# CPU_EBI1_FPGA_Memory.net
KiCad netlist of a schematic drawn in Altium Designer
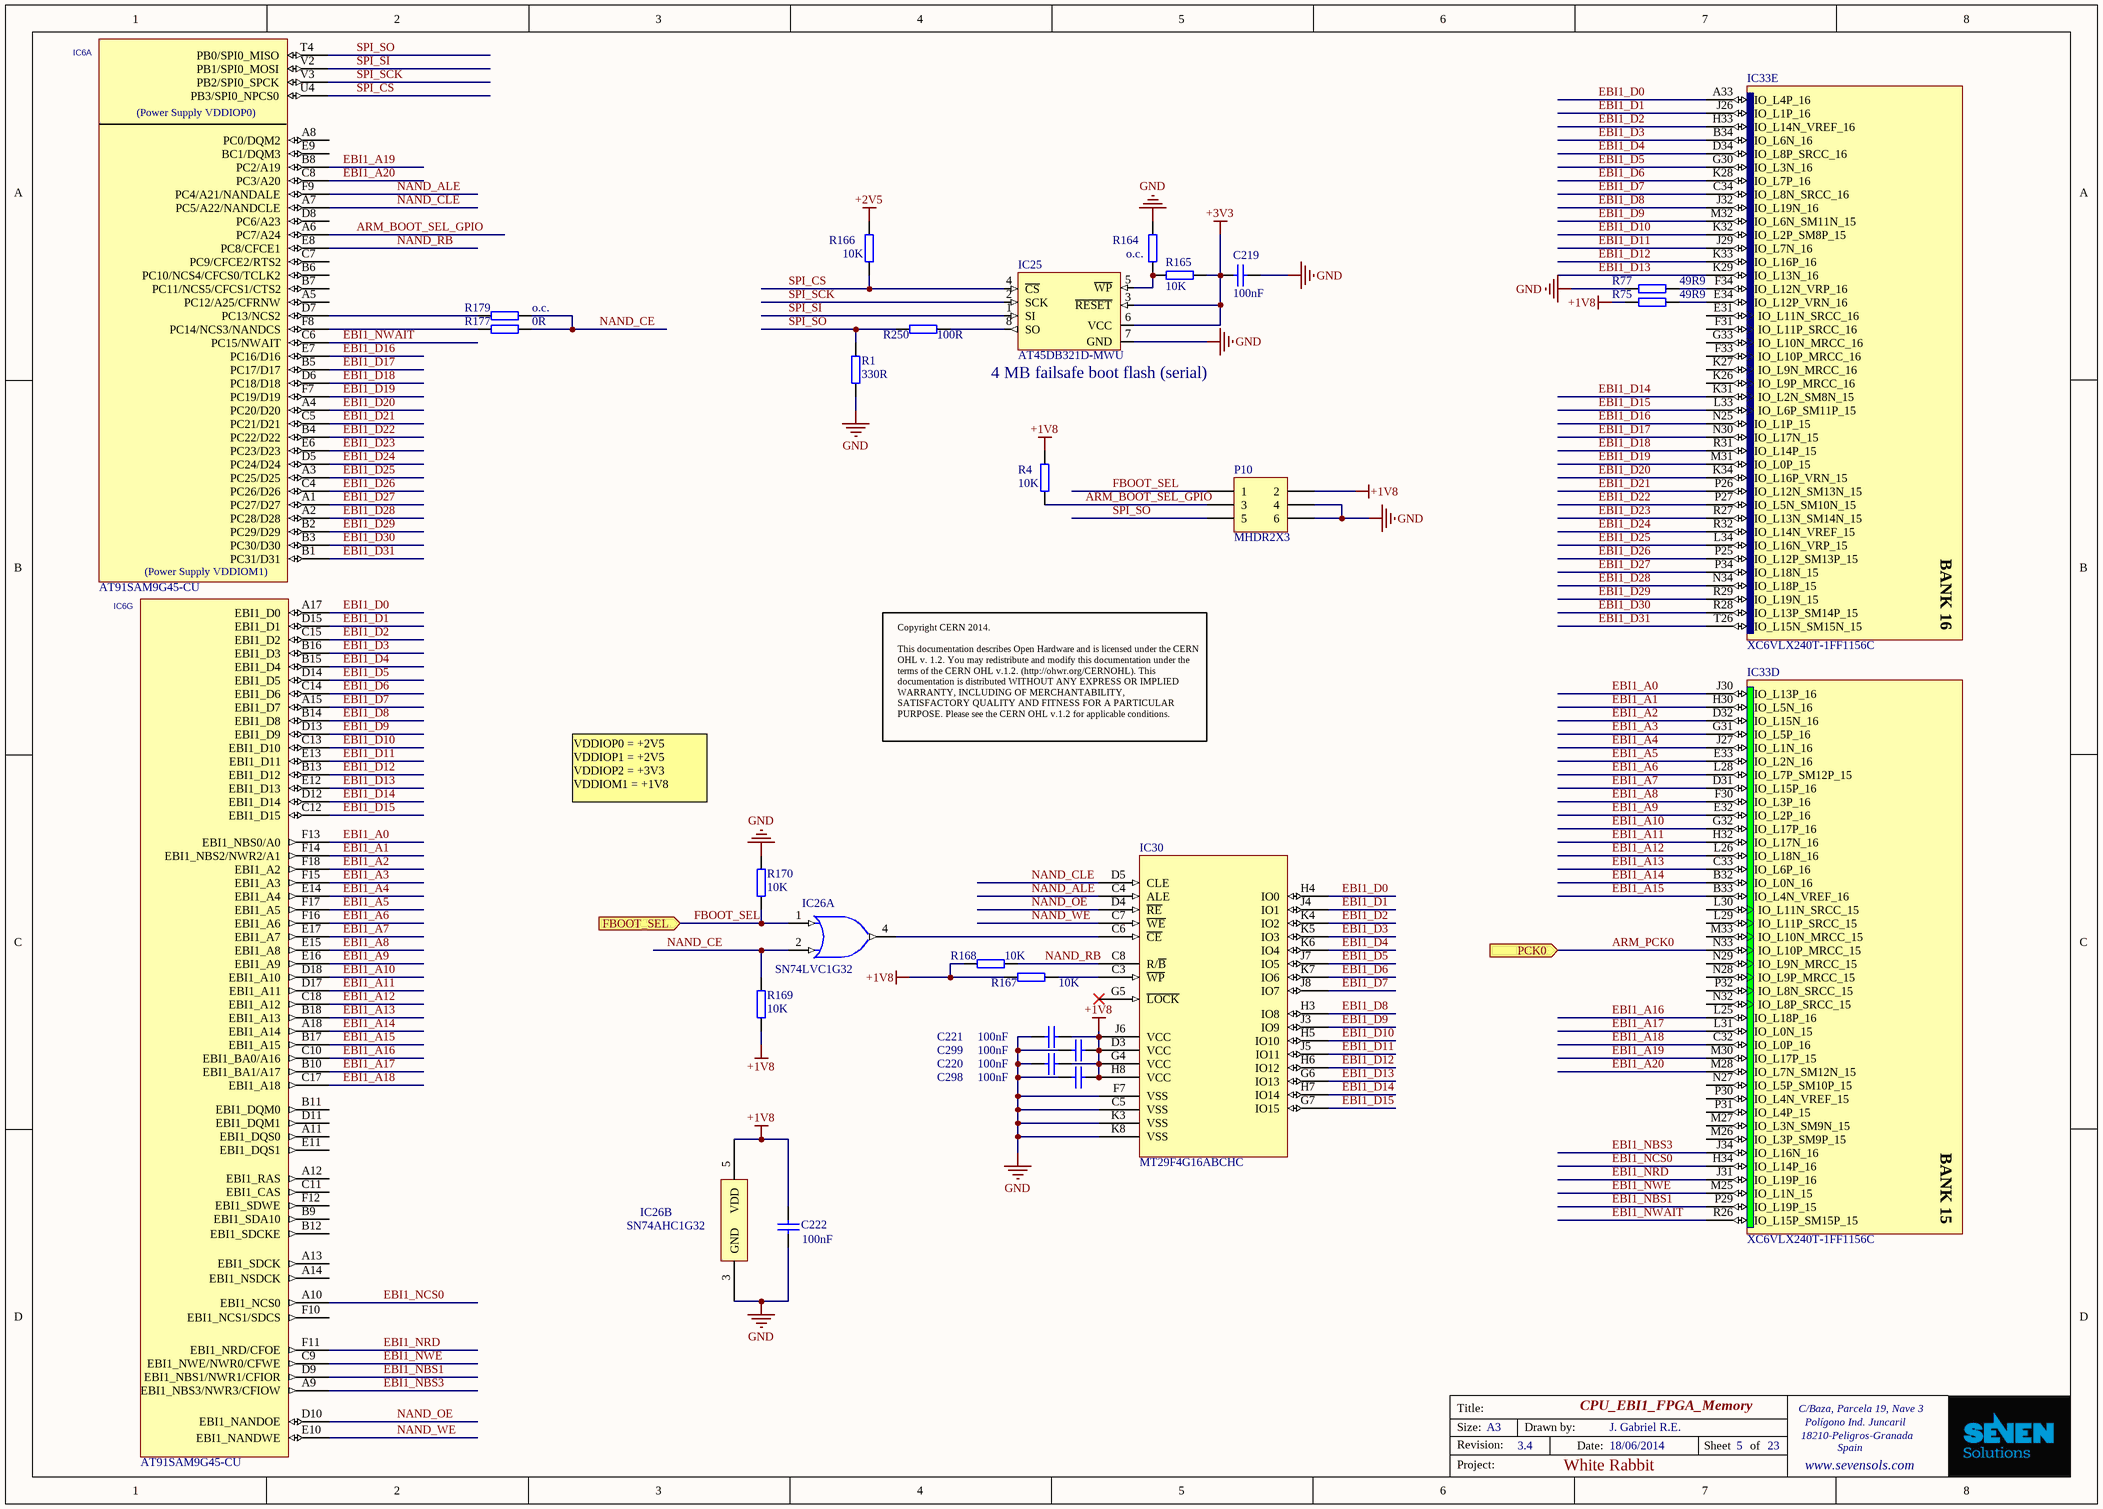
[diagram p0: CPU_EBI1_FPGA_Memory.SchDoc]

(export (version "E")
  (design (tool "Eeschema 10.0.6"))
  (components
    (comp (ref "C219")
      (value "100nF")
      (footprint "CC1005-0402")
      (description "Capacitor")
      (fields
        (field (name "TOLERANCE") "±10%")
        (field (name "VOLTAGE") "16V")
        (field (name "PUBLISHER") "Altium Limited")
      )
      (libsource (lib "wr_switch") (part "Cap"))
    )
    (comp (ref "C220")
      (value "100nF")
      (footprint "CC1005-0402")
      (description "Capacitor")
      (fields
        (field (name "TOLERANCE") "±10%")
        (field (name "VOLTAGE") "16V")
        (field (name "PUBLISHER") "Altium Limited")
      )
      (libsource (lib "wr_switch") (part "Cap"))
    )
    (comp (ref "C221")
      (value "100nF")
      (footprint "CC1005-0402")
      (description "Capacitor")
      (fields
        (field (name "TOLERANCE") "±10%")
        (field (name "VOLTAGE") "16V")
        (field (name "PUBLISHER") "Altium Limited")
      )
      (libsource (lib "wr_switch") (part "Cap"))
    )
    (comp (ref "C222")
      (value "100nF")
      (footprint "CC1005-0402")
      (description "Capacitor")
      (fields
        (field (name "TOLERANCE") "±10%")
        (field (name "VOLTAGE") "16V")
        (field (name "PUBLISHER") "Altium Limited")
      )
      (libsource (lib "wr_switch") (part "Cap"))
    )
    (comp (ref "C298")
      (value "100nF")
      (footprint "CC1005-0402")
      (description "Capacitor")
      (fields
        (field (name "TOLERANCE") "±10%")
        (field (name "VOLTAGE") "16V")
        (field (name "PUBLISHER") "Altium Limited")
      )
      (libsource (lib "wr_switch") (part "Cap"))
    )
    (comp (ref "C299")
      (value "100nF")
      (footprint "CC1005-0402")
      (description "Capacitor")
      (fields
        (field (name "TOLERANCE") "±10%")
        (field (name "VOLTAGE") "16V")
        (field (name "PUBLISHER") "Altium Limited")
      )
      (libsource (lib "wr_switch") (part "Cap"))
    )
    (comp (ref "IC6")
      (value "AT91SAM9G45-CU")
      (footprint "TFBGA324")
      (description "Atmel 400MHz ARM926 MCU")
      (libsource (lib "wr_switch") (part "AT91SAM9G45-CU"))
    )
    (comp (ref "IC25")
      (value "AT45DB321D-MWU")
      (footprint "7S_WR:8MW_8CN3_Merge")
      (description "64-megabit 2.7V, Dual-Interface DataFlash")
      (libsource (lib "wr_switch") (part "AT45DB642D"))
    )
    (comp (ref "IC26")
      (value "SN74LVC1G32")
      (footprint "SOT23-5AL")
      (description "TI single OR gate")
      (libsource (lib "wr_switch") (part "SN74AHC1G32"))
    )
    (comp (ref "IC30")
      (value "MT29F4G16ABCHC")
      (footprint "7S_WR:VFBGA63")
      (description "NAND Flash 256Mx16, 1.8V Asynch/Page")
      (libsource (lib "wr_switch") (part "MT29F4G16ABCHC"))
    )
    (comp (ref "IC33")
      (value "XC6VLX240T-1FF1156C")
      (footprint "FF1156")
      (fields (field (name "PUBLISHER") "Altium Limited"))
      (libsource (lib "") (part "XC6VLX240T-1FF1156C_1"))
    )
    (comp (ref "P10")
      (value "MHDR2X3")
      (footprint "7S_WR:MHDR2X3_1.27mm")
      (description "SMD Header, 3-Pin, Dual row, 2.54mm pitch")
      (libsource (lib "Miscellaneous Connectors") (part "MHDR2X3"))
    )
    (comp (ref "R1")
      (value "330R")
      (footprint "0402")
      (description "SMD Resistor")
      (fields (field (name "TOLERANCE") "±1%"))
      (libsource (lib "wr_switch") (part "RES_SMD"))
    )
    (comp (ref "R4")
      (value "10K")
      (footprint "0402")
      (description "SMD Resistor")
      (fields (field (name "TOLERANCE") "±1%"))
      (libsource (lib "wr_switch") (part "RES_SMD"))
    )
    (comp (ref "R75")
      (value "49R9")
      (footprint "0402")
      (description "SMD Resistor")
      (fields (field (name "TOLERANCE") "±1%"))
      (libsource (lib "wr_switch") (part "RES_SMD"))
    )
    (comp (ref "R77")
      (value "49R9")
      (footprint "0402")
      (description "SMD Resistor")
      (fields (field (name "TOLERANCE") "±1%"))
      (libsource (lib "wr_switch") (part "RES_SMD"))
    )
    (comp (ref "R164")
      (value "o.c.")
      (footprint "0402")
      (description "SMD Resistor")
      (libsource (lib "wr_switch") (part "RES_SMD"))
    )
    (comp (ref "R165")
      (value "10K")
      (footprint "0402")
      (description "SMD Resistor")
      (fields (field (name "TOLERANCE") "±1%"))
      (libsource (lib "wr_switch") (part "RES_SMD"))
    )
    (comp (ref "R166")
      (value "10K")
      (footprint "0402")
      (description "SMD Resistor")
      (fields (field (name "TOLERANCE") "±1%"))
      (libsource (lib "wr_switch") (part "RES_SMD"))
    )
    (comp (ref "R167")
      (value "10K")
      (footprint "0402")
      (description "SMD Resistor")
      (fields (field (name "TOLERANCE") "±1%"))
      (libsource (lib "wr_switch") (part "RES_SMD"))
    )
    (comp (ref "R168")
      (value "10K")
      (footprint "0402")
      (description "SMD Resistor")
      (fields (field (name "TOLERANCE") "±1%"))
      (libsource (lib "wr_switch") (part "RES_SMD"))
    )
    (comp (ref "R169")
      (value "10K")
      (footprint "0402")
      (description "SMD Resistor")
      (fields (field (name "TOLERANCE") "±1%"))
      (libsource (lib "wr_switch") (part "RES_SMD"))
    )
    (comp (ref "R170")
      (value "10K")
      (footprint "0402")
      (description "SMD Resistor")
      (fields (field (name "TOLERANCE") "±1%"))
      (libsource (lib "wr_switch") (part "RES_SMD"))
    )
    (comp (ref "R177")
      (value "0R")
      (footprint "0603")
      (description "SMD Resistor")
      (libsource (lib "wr_switch") (part "RES_SMD"))
    )
    (comp (ref "R179")
      (value "o.c.")
      (footprint "0402")
      (description "SMD Resistor")
      (libsource (lib "wr_switch") (part "RES_SMD"))
    )
    (comp (ref "R250")
      (value "100R")
      (footprint "0402")
      (description "SMD Resistor")
      (fields (field (name "TOLERANCE") "±1%"))
      (libsource (lib "wr_switch") (part "RES_SMD"))
    )
  )
  (nets
    (net (code "1") (name "+1V8") (class "Default")
      (node (ref "C220") (pin "1") (pinfunction "1_1") (pintype "passive"))
      (node (ref "C221") (pin "1") (pinfunction "1_1") (pintype "passive"))
      (node (ref "C222") (pin "2") (pinfunction "2_2") (pintype "passive"))
      (node (ref "C298") (pin "1") (pinfunction "1_1") (pintype "passive"))
      (node (ref "C299") (pin "1") (pinfunction "1_1") (pintype "passive"))
      (node (ref "IC26") (pin "5") (pinfunction "VDD_5") (pintype "passive"))
      (node (ref "IC30") (pin "D3") (pinfunction "VCC_D3") (pintype "power_in"))
      (node (ref "IC30") (pin "G4") (pinfunction "VCC_G4") (pintype "power_in"))
      (node (ref "IC30") (pin "H8") (pinfunction "VCC_H8") (pintype "power_in"))
      (node (ref "IC30") (pin "J6") (pinfunction "VCC_J6") (pintype "power_in"))
      (node (ref "P10") (pin "2") (pinfunction "2_2") (pintype "passive"))
      (node (ref "R167") (pin "2") (pinfunction "2_2") (pintype "passive"))
      (node (ref "R168") (pin "2") (pinfunction "2_2") (pintype "passive"))
      (node (ref "R169") (pin "2") (pinfunction "2_2") (pintype "passive"))
      (node (ref "R4") (pin "2") (pinfunction "2_2") (pintype "passive"))
      (node (ref "R75") (pin "2") (pinfunction "2_2") (pintype "passive"))
    )
    (net (code "2") (name "+2V5") (class "Default")
      (node (ref "R166") (pin "2") (pinfunction "2_2") (pintype "passive"))
    )
    (net (code "3") (name "+3V3") (class "Default")
      (node (ref "C219") (pin "1") (pinfunction "1_1") (pintype "passive"))
      (node (ref "IC25") (pin "3") (pinfunction "~{RESET}_3") (pintype "input"))
      (node (ref "IC25") (pin "6") (pinfunction "VCC_6") (pintype "power_in"))
      (node (ref "R165") (pin "2") (pinfunction "2_2") (pintype "passive"))
    )
    (net (code "4") (name "/ARM_BOOT_SEL_GPIO") (class "Default")
      (node (ref "IC6") (pin "A6") (pinfunction "PC7/A24_A6") (pintype "bidirectional"))
      (node (ref "P10") (pin "3") (pinfunction "3_3") (pintype "passive"))
      (node (ref "R4") (pin "1") (pinfunction "1_1") (pintype "passive"))
    )
    (net (code "5") (name "/ARM_PCK0") (class "Default")
      (node (ref "IC33") (pin "N33") (pinfunction "IO_L10P_MRCC_15_N33") (pintype "bidirectional"))
    )
    (net (code "6") (name "/EBI1_A0") (class "Default")
      (node (ref "IC33") (pin "J30") (pinfunction "IO_L13P_16_J30") (pintype "bidirectional"))
      (node (ref "IC6") (pin "F13") (pinfunction "EBI1_NBS0/A0_F13") (pintype "output"))
    )
    (net (code "7") (name "/EBI1_A1") (class "Default")
      (node (ref "IC33") (pin "H30") (pinfunction "IO_L5N_16_H30") (pintype "bidirectional"))
      (node (ref "IC6") (pin "F14") (pinfunction "EBI1_NBS2/NWR2/A1_F14") (pintype "output"))
    )
    (net (code "8") (name "/EBI1_A2") (class "Default")
      (node (ref "IC33") (pin "D32") (pinfunction "IO_L15N_16_D32") (pintype "bidirectional"))
      (node (ref "IC6") (pin "F18") (pinfunction "EBI1_A2_F18") (pintype "output"))
    )
    (net (code "9") (name "/EBI1_A3") (class "Default")
      (node (ref "IC33") (pin "G31") (pinfunction "IO_L5P_16_G31") (pintype "bidirectional"))
      (node (ref "IC6") (pin "F15") (pinfunction "EBI1_A3_F15") (pintype "output"))
    )
    (net (code "10") (name "/EBI1_A4") (class "Default")
      (node (ref "IC33") (pin "J27") (pinfunction "IO_L1N_16_J27") (pintype "bidirectional"))
      (node (ref "IC6") (pin "E14") (pinfunction "EBI1_A4_E14") (pintype "output"))
    )
    (net (code "11") (name "/EBI1_A5") (class "Default")
      (node (ref "IC33") (pin "E33") (pinfunction "IO_L2N_16_E33") (pintype "bidirectional"))
      (node (ref "IC6") (pin "F17") (pinfunction "EBI1_A5_F17") (pintype "output"))
    )
    (net (code "12") (name "/EBI1_A6") (class "Default")
      (node (ref "IC33") (pin "L28") (pinfunction "IO_L7P_SM12P_15_L28") (pintype "bidirectional"))
      (node (ref "IC6") (pin "F16") (pinfunction "EBI1_A6_F16") (pintype "output"))
    )
    (net (code "13") (name "/EBI1_A7") (class "Default")
      (node (ref "IC33") (pin "D31") (pinfunction "IO_L15P_16_D31") (pintype "bidirectional"))
      (node (ref "IC6") (pin "E17") (pinfunction "EBI1_A7_E17") (pintype "output"))
    )
    (net (code "14") (name "/EBI1_A8") (class "Default")
      (node (ref "IC33") (pin "F30") (pinfunction "IO_L3P_16_F30") (pintype "bidirectional"))
      (node (ref "IC6") (pin "E15") (pinfunction "EBI1_A8_E15") (pintype "output"))
    )
    (net (code "15") (name "/EBI1_A9") (class "Default")
      (node (ref "IC33") (pin "E32") (pinfunction "IO_L2P_16_E32") (pintype "bidirectional"))
      (node (ref "IC6") (pin "E16") (pinfunction "EBI1_A9_E16") (pintype "output"))
    )
    (net (code "16") (name "/EBI1_A10") (class "Default")
      (node (ref "IC33") (pin "G32") (pinfunction "IO_L17P_16_G32") (pintype "bidirectional"))
      (node (ref "IC6") (pin "D18") (pinfunction "EBI1_A10_D18") (pintype "output"))
    )
    (net (code "17") (name "/EBI1_A11") (class "Default")
      (node (ref "IC33") (pin "H32") (pinfunction "IO_L17N_16_H32") (pintype "bidirectional"))
      (node (ref "IC6") (pin "D17") (pinfunction "EBI1_A11_D17") (pintype "output"))
    )
    (net (code "18") (name "/EBI1_A12") (class "Default")
      (node (ref "IC33") (pin "L26") (pinfunction "IO_L18N_16_L26") (pintype "bidirectional"))
      (node (ref "IC6") (pin "C18") (pinfunction "EBI1_A12_C18") (pintype "output"))
    )
    (net (code "19") (name "/EBI1_A13") (class "Default")
      (node (ref "IC33") (pin "C33") (pinfunction "IO_L6P_16_C33") (pintype "bidirectional"))
      (node (ref "IC6") (pin "B18") (pinfunction "EBI1_A13_B18") (pintype "output"))
    )
    (net (code "20") (name "/EBI1_A14") (class "Default")
      (node (ref "IC33") (pin "B32") (pinfunction "IO_L0N_16_B32") (pintype "bidirectional"))
      (node (ref "IC6") (pin "A18") (pinfunction "EBI1_A14_A18") (pintype "output"))
    )
    (net (code "21") (name "/EBI1_A15") (class "Default")
      (node (ref "IC33") (pin "B33") (pinfunction "IO_L4N_VREF_16_B33") (pintype "bidirectional"))
      (node (ref "IC6") (pin "B17") (pinfunction "EBI1_A15_B17") (pintype "output"))
    )
    (net (code "22") (name "/EBI1_A16") (class "Default")
      (node (ref "IC33") (pin "L25") (pinfunction "IO_L18P_16_L25") (pintype "bidirectional"))
      (node (ref "IC6") (pin "C10") (pinfunction "EBI1_BA0/A16_C10") (pintype "output"))
    )
    (net (code "23") (name "/EBI1_A17") (class "Default")
      (node (ref "IC33") (pin "L31") (pinfunction "IO_L0N_15_L31") (pintype "bidirectional"))
      (node (ref "IC6") (pin "B10") (pinfunction "EBI1_BA1/A17_B10") (pintype "output"))
    )
    (net (code "24") (name "/EBI1_A18") (class "Default")
      (node (ref "IC33") (pin "C32") (pinfunction "IO_L0P_16_C32") (pintype "bidirectional"))
      (node (ref "IC6") (pin "C17") (pinfunction "EBI1_A18_C17") (pintype "output"))
    )
    (net (code "25") (name "/EBI1_A19") (class "Default")
      (node (ref "IC33") (pin "M30") (pinfunction "IO_L17P_15_M30") (pintype "bidirectional"))
      (node (ref "IC6") (pin "B8") (pinfunction "PC2/A19_B8") (pintype "bidirectional"))
    )
    (net (code "26") (name "/EBI1_A20") (class "Default")
      (node (ref "IC33") (pin "M28") (pinfunction "IO_L7N_SM12N_15_M28") (pintype "bidirectional"))
      (node (ref "IC6") (pin "C8") (pinfunction "PC3/A20_C8") (pintype "bidirectional"))
    )
    (net (code "27") (name "/EBI1_D0") (class "Default")
      (node (ref "IC30") (pin "H4") (pinfunction "IO0_H4") (pintype "bidirectional"))
      (node (ref "IC33") (pin "A33") (pinfunction "IO_L4P_16_A33") (pintype "bidirectional"))
      (node (ref "IC6") (pin "A17") (pinfunction "EBI1_D0_A17") (pintype "bidirectional"))
    )
    (net (code "28") (name "/EBI1_D1") (class "Default")
      (node (ref "IC30") (pin "J4") (pinfunction "IO1_J4") (pintype "bidirectional"))
      (node (ref "IC33") (pin "J26") (pinfunction "IO_L1P_16_J26") (pintype "bidirectional"))
      (node (ref "IC6") (pin "D15") (pinfunction "EBI1_D1_D15") (pintype "bidirectional"))
    )
    (net (code "29") (name "/EBI1_D2") (class "Default")
      (node (ref "IC30") (pin "K4") (pinfunction "IO2_K4") (pintype "bidirectional"))
      (node (ref "IC33") (pin "H33") (pinfunction "IO_L14N_VREF_16_H33") (pintype "bidirectional"))
      (node (ref "IC6") (pin "C15") (pinfunction "EBI1_D2_C15") (pintype "bidirectional"))
    )
    (net (code "30") (name "/EBI1_D3") (class "Default")
      (node (ref "IC30") (pin "K5") (pinfunction "IO3_K5") (pintype "bidirectional"))
      (node (ref "IC33") (pin "B34") (pinfunction "IO_L6N_16_B34") (pintype "bidirectional"))
      (node (ref "IC6") (pin "B16") (pinfunction "EBI1_D3_B16") (pintype "bidirectional"))
    )
    (net (code "31") (name "/EBI1_D4") (class "Default")
      (node (ref "IC30") (pin "K6") (pinfunction "IO4_K6") (pintype "bidirectional"))
      (node (ref "IC33") (pin "D34") (pinfunction "IO_L8P_SRCC_16_D34") (pintype "bidirectional"))
      (node (ref "IC6") (pin "B15") (pinfunction "EBI1_D4_B15") (pintype "bidirectional"))
    )
    (net (code "32") (name "/EBI1_D5") (class "Default")
      (node (ref "IC30") (pin "J7") (pinfunction "IO5_J7") (pintype "bidirectional"))
      (node (ref "IC33") (pin "G30") (pinfunction "IO_L3N_16_G30") (pintype "bidirectional"))
      (node (ref "IC6") (pin "D14") (pinfunction "EBI1_D5_D14") (pintype "bidirectional"))
    )
    (net (code "33") (name "/EBI1_D6") (class "Default")
      (node (ref "IC30") (pin "K7") (pinfunction "IO6_K7") (pintype "bidirectional"))
      (node (ref "IC33") (pin "K28") (pinfunction "IO_L7P_16_K28") (pintype "bidirectional"))
      (node (ref "IC6") (pin "C14") (pinfunction "EBI1_D6_C14") (pintype "bidirectional"))
    )
    (net (code "34") (name "/EBI1_D7") (class "Default")
      (node (ref "IC30") (pin "J8") (pinfunction "IO7_J8") (pintype "bidirectional"))
      (node (ref "IC33") (pin "C34") (pinfunction "IO_L8N_SRCC_16_C34") (pintype "bidirectional"))
      (node (ref "IC6") (pin "A15") (pinfunction "EBI1_D7_A15") (pintype "bidirectional"))
    )
    (net (code "35") (name "/EBI1_D8") (class "Default")
      (node (ref "IC30") (pin "H3") (pinfunction "IO8_H3") (pintype "bidirectional"))
      (node (ref "IC33") (pin "J32") (pinfunction "IO_L19N_16_J32") (pintype "bidirectional"))
      (node (ref "IC6") (pin "B14") (pinfunction "EBI1_D8_B14") (pintype "bidirectional"))
    )
    (net (code "36") (name "/EBI1_D9") (class "Default")
      (node (ref "IC30") (pin "J3") (pinfunction "IO9_J3") (pintype "bidirectional"))
      (node (ref "IC33") (pin "M32") (pinfunction "IO_L6N_SM11N_15_M32") (pintype "bidirectional"))
      (node (ref "IC6") (pin "D13") (pinfunction "EBI1_D9_D13") (pintype "bidirectional"))
    )
    (net (code "37") (name "/EBI1_D10") (class "Default")
      (node (ref "IC30") (pin "H5") (pinfunction "IO10_H5") (pintype "bidirectional"))
      (node (ref "IC33") (pin "K32") (pinfunction "IO_L2P_SM8P_15_K32") (pintype "bidirectional"))
      (node (ref "IC6") (pin "C13") (pinfunction "EBI1_D10_C13") (pintype "bidirectional"))
    )
    (net (code "38") (name "/EBI1_D11") (class "Default")
      (node (ref "IC30") (pin "J5") (pinfunction "IO11_J5") (pintype "bidirectional"))
      (node (ref "IC33") (pin "J29") (pinfunction "IO_L7N_16_J29") (pintype "bidirectional"))
      (node (ref "IC6") (pin "E13") (pinfunction "EBI1_D11_E13") (pintype "bidirectional"))
    )
    (net (code "39") (name "/EBI1_D12") (class "Default")
      (node (ref "IC30") (pin "H6") (pinfunction "IO12_H6") (pintype "bidirectional"))
      (node (ref "IC33") (pin "K33") (pinfunction "IO_L16P_16_K33") (pintype "bidirectional"))
      (node (ref "IC6") (pin "B13") (pinfunction "EBI1_D12_B13") (pintype "bidirectional"))
    )
    (net (code "40") (name "/EBI1_D13") (class "Default")
      (node (ref "IC30") (pin "G6") (pinfunction "IO13_G6") (pintype "bidirectional"))
      (node (ref "IC33") (pin "K29") (pinfunction "IO_L13N_16_K29") (pintype "bidirectional"))
      (node (ref "IC6") (pin "E12") (pinfunction "EBI1_D13_E12") (pintype "bidirectional"))
    )
    (net (code "41") (name "/EBI1_D14") (class "Default")
      (node (ref "IC30") (pin "H7") (pinfunction "IO14_H7") (pintype "bidirectional"))
      (node (ref "IC33") (pin "K31") (pinfunction "IO_L2N_SM8N_15_K31") (pintype "bidirectional"))
      (node (ref "IC6") (pin "D12") (pinfunction "EBI1_D14_D12") (pintype "bidirectional"))
    )
    (net (code "42") (name "/EBI1_D15") (class "Default")
      (node (ref "IC30") (pin "G7") (pinfunction "IO15_G7") (pintype "bidirectional"))
      (node (ref "IC33") (pin "L33") (pinfunction "IO_L6P_SM11P_15_L33") (pintype "bidirectional"))
      (node (ref "IC6") (pin "C12") (pinfunction "EBI1_D15_C12") (pintype "bidirectional"))
    )
    (net (code "43") (name "/EBI1_D16") (class "Default")
      (node (ref "IC33") (pin "N25") (pinfunction "IO_L1P_15_N25") (pintype "bidirectional"))
      (node (ref "IC6") (pin "E7") (pinfunction "PC16/D16_E7") (pintype "bidirectional"))
    )
    (net (code "44") (name "/EBI1_D17") (class "Default")
      (node (ref "IC33") (pin "N30") (pinfunction "IO_L17N_15_N30") (pintype "bidirectional"))
      (node (ref "IC6") (pin "B5") (pinfunction "PC17/D17_B5") (pintype "bidirectional"))
    )
    (net (code "45") (name "/EBI1_D18") (class "Default")
      (node (ref "IC33") (pin "R31") (pinfunction "IO_L14P_15_R31") (pintype "bidirectional"))
      (node (ref "IC6") (pin "D6") (pinfunction "PC18/D18_D6") (pintype "bidirectional"))
    )
    (net (code "46") (name "/EBI1_D19") (class "Default")
      (node (ref "IC33") (pin "M31") (pinfunction "IO_L0P_15_M31") (pintype "bidirectional"))
      (node (ref "IC6") (pin "F7") (pinfunction "PC19/D19_F7") (pintype "bidirectional"))
    )
    (net (code "47") (name "/EBI1_D20") (class "Default")
      (node (ref "IC33") (pin "K34") (pinfunction "IO_L16P_VRN_15_K34") (pintype "bidirectional"))
      (node (ref "IC6") (pin "A4") (pinfunction "PC20/D20_A4") (pintype "bidirectional"))
    )
    (net (code "48") (name "/EBI1_D21") (class "Default")
      (node (ref "IC33") (pin "P26") (pinfunction "IO_L12N_SM13N_15_P26") (pintype "bidirectional"))
      (node (ref "IC6") (pin "C5") (pinfunction "PC21/D21_C5") (pintype "bidirectional"))
    )
    (net (code "49") (name "/EBI1_D22") (class "Default")
      (node (ref "IC33") (pin "P27") (pinfunction "IO_L5N_SM10N_15_P27") (pintype "bidirectional"))
      (node (ref "IC6") (pin "B4") (pinfunction "PC22/D22_B4") (pintype "bidirectional"))
    )
    (net (code "50") (name "/EBI1_D23") (class "Default")
      (node (ref "IC33") (pin "R27") (pinfunction "IO_L13N_SM14N_15_R27") (pintype "bidirectional"))
      (node (ref "IC6") (pin "E6") (pinfunction "PC23/D23_E6") (pintype "bidirectional"))
    )
    (net (code "51") (name "/EBI1_D24") (class "Default")
      (node (ref "IC33") (pin "R32") (pinfunction "IO_L14N_VREF_15_R32") (pintype "bidirectional"))
      (node (ref "IC6") (pin "D5") (pinfunction "PC24/D24_D5") (pintype "bidirectional"))
    )
    (net (code "52") (name "/EBI1_D25") (class "Default")
      (node (ref "IC33") (pin "L34") (pinfunction "IO_L16N_VRP_15_L34") (pintype "bidirectional"))
      (node (ref "IC6") (pin "A3") (pinfunction "PC25/D25_A3") (pintype "bidirectional"))
    )
    (net (code "53") (name "/EBI1_D26") (class "Default")
      (node (ref "IC33") (pin "P25") (pinfunction "IO_L12P_SM13P_15_P25") (pintype "bidirectional"))
      (node (ref "IC6") (pin "C4") (pinfunction "PC26/D26_C4") (pintype "bidirectional"))
    )
    (net (code "54") (name "/EBI1_D27") (class "Default")
      (node (ref "IC33") (pin "P34") (pinfunction "IO_L18N_15_P34") (pintype "bidirectional"))
      (node (ref "IC6") (pin "A1") (pinfunction "PC27/D27_A1") (pintype "bidirectional"))
    )
    (net (code "55") (name "/EBI1_D28") (class "Default")
      (node (ref "IC33") (pin "N34") (pinfunction "IO_L18P_15_N34") (pintype "bidirectional"))
      (node (ref "IC6") (pin "A2") (pinfunction "PC28/D28_A2") (pintype "bidirectional"))
    )
    (net (code "56") (name "/EBI1_D29") (class "Default")
      (node (ref "IC33") (pin "R29") (pinfunction "IO_L19N_15_R29") (pintype "bidirectional"))
      (node (ref "IC6") (pin "B2") (pinfunction "PC29/D29_B2") (pintype "bidirectional"))
    )
    (net (code "57") (name "/EBI1_D30") (class "Default")
      (node (ref "IC33") (pin "R28") (pinfunction "IO_L13P_SM14P_15_R28") (pintype "bidirectional"))
      (node (ref "IC6") (pin "B3") (pinfunction "PC30/D30_B3") (pintype "bidirectional"))
    )
    (net (code "58") (name "/EBI1_D31") (class "Default")
      (node (ref "IC33") (pin "T26") (pinfunction "IO_L15N_SM15N_15_T26") (pintype "bidirectional"))
      (node (ref "IC6") (pin "B1") (pinfunction "PC31/D31_B1") (pintype "bidirectional"))
    )
    (net (code "59") (name "/EBI1_NBS1") (class "Default")
      (node (ref "IC33") (pin "P29") (pinfunction "IO_L19P_15_P29") (pintype "bidirectional"))
      (node (ref "IC6") (pin "D9") (pinfunction "EBI1_NBS1/NWR1/CFIOR_D9") (pintype "output"))
    )
    (net (code "60") (name "/EBI1_NBS3") (class "Default")
      (node (ref "IC33") (pin "J34") (pinfunction "IO_L16N_16_J34") (pintype "bidirectional"))
      (node (ref "IC6") (pin "A9") (pinfunction "EBI1_NBS3/NWR3/CFIOW_A9") (pintype "output"))
    )
    (net (code "61") (name "/EBI1_NCS0") (class "Default")
      (node (ref "IC33") (pin "H34") (pinfunction "IO_L14P_16_H34") (pintype "bidirectional"))
      (node (ref "IC6") (pin "A10") (pinfunction "EBI1_NCS0_A10") (pintype "output"))
    )
    (net (code "62") (name "/EBI1_NRD") (class "Default")
      (node (ref "IC33") (pin "J31") (pinfunction "IO_L19P_16_J31") (pintype "bidirectional"))
      (node (ref "IC6") (pin "F11") (pinfunction "EBI1_NRD/CFOE_F11") (pintype "output"))
    )
    (net (code "63") (name "/EBI1_NWAIT") (class "Default")
      (node (ref "IC33") (pin "R26") (pinfunction "IO_L15P_SM15P_15_R26") (pintype "bidirectional"))
      (node (ref "IC6") (pin "C6") (pinfunction "PC15/NWAIT_C6") (pintype "bidirectional"))
    )
    (net (code "64") (name "/EBI1_NWE") (class "Default")
      (node (ref "IC33") (pin "M25") (pinfunction "IO_L1N_15_M25") (pintype "bidirectional"))
      (node (ref "IC6") (pin "C9") (pinfunction "EBI1_NWE/NWR0/CFWE_C9") (pintype "output"))
    )
    (net (code "65") (name "/FBOOT_SEL") (class "Default")
      (node (ref "IC26") (pin "1") (pinfunction "A_1") (pintype "input"))
      (node (ref "P10") (pin "1") (pinfunction "1_1") (pintype "passive"))
      (node (ref "R170") (pin "1") (pinfunction "1_1") (pintype "passive"))
    )
    (net (code "66") (name "/NAND_ALE") (class "Default")
      (node (ref "IC30") (pin "C4") (pinfunction "ALE_C4") (pintype "input"))
      (node (ref "IC6") (pin "F9") (pinfunction "PC4/A21/NANDALE_F9") (pintype "bidirectional"))
    )
    (net (code "67") (name "/NAND_CE") (class "Default")
      (node (ref "IC26") (pin "2") (pinfunction "B_2") (pintype "input"))
      (node (ref "R169") (pin "1") (pinfunction "1_1") (pintype "passive"))
      (node (ref "R177") (pin "1") (pinfunction "1_1") (pintype "passive"))
      (node (ref "R179") (pin "1") (pinfunction "1_1") (pintype "passive"))
    )
    (net (code "68") (name "/NAND_CLE") (class "Default")
      (node (ref "IC30") (pin "D5") (pinfunction "CLE_D5") (pintype "input"))
      (node (ref "IC6") (pin "A7") (pinfunction "PC5/A22/NANDCLE_A7") (pintype "bidirectional"))
    )
    (net (code "69") (name "/NAND_OE") (class "Default")
      (node (ref "IC30") (pin "D4") (pinfunction "~{RE}_D4") (pintype "input"))
      (node (ref "IC6") (pin "D10") (pinfunction "EBI1_NANDOE_D10") (pintype "bidirectional"))
    )
    (net (code "70") (name "/NAND_RB") (class "Default")
      (node (ref "IC30") (pin "C8") (pinfunction "R/~{B}_C8") (pintype "open_collector"))
      (node (ref "IC6") (pin "E8") (pinfunction "PC8/CFCE1_E8") (pintype "bidirectional"))
      (node (ref "R168") (pin "1") (pinfunction "1_1") (pintype "passive"))
    )
    (net (code "71") (name "/NAND_WE") (class "Default")
      (node (ref "IC30") (pin "C7") (pinfunction "~{WE}_C7") (pintype "input"))
      (node (ref "IC6") (pin "E10") (pinfunction "EBI1_NANDWE_E10") (pintype "bidirectional"))
    )
    (net (code "72") (name "/SPI_CS") (class "Default")
      (node (ref "IC25") (pin "4") (pinfunction "~{CS}_4") (pintype "input"))
      (node (ref "IC6") (pin "U4") (pinfunction "PB3/SPI0_NPCS0_U4") (pintype "bidirectional"))
      (node (ref "R166") (pin "1") (pinfunction "1_1") (pintype "passive"))
    )
    (net (code "73") (name "/SPI_SCK") (class "Default")
      (node (ref "IC25") (pin "2") (pinfunction "SCK_2") (pintype "input"))
      (node (ref "IC6") (pin "V3") (pinfunction "PB2/SPI0_SPCK_V3") (pintype "bidirectional"))
    )
    (net (code "74") (name "/SPI_SI") (class "Default")
      (node (ref "IC25") (pin "1") (pinfunction "SI_1") (pintype "input"))
      (node (ref "IC6") (pin "V2") (pinfunction "PB1/SPI0_MOSI_V2") (pintype "bidirectional"))
    )
    (net (code "75") (name "/SPI_SO") (class "Default")
      (node (ref "IC6") (pin "T4") (pinfunction "PB0/SPI0_MISO_T4") (pintype "bidirectional"))
      (node (ref "P10") (pin "5") (pinfunction "5_5") (pintype "passive"))
      (node (ref "R1") (pin "2") (pinfunction "2_2") (pintype "passive"))
      (node (ref "R250") (pin "2") (pinfunction "2_2") (pintype "passive"))
    )
    (net (code "76") (name "GND") (class "Default")
      (node (ref "C219") (pin "2") (pinfunction "2_2") (pintype "passive"))
      (node (ref "C220") (pin "2") (pinfunction "2_2") (pintype "passive"))
      (node (ref "C221") (pin "2") (pinfunction "2_2") (pintype "passive"))
      (node (ref "C222") (pin "1") (pinfunction "1_1") (pintype "passive"))
      (node (ref "C298") (pin "2") (pinfunction "2_2") (pintype "passive"))
      (node (ref "C299") (pin "2") (pinfunction "2_2") (pintype "passive"))
      (node (ref "IC25") (pin "7") (pinfunction "GND_7") (pintype "power_in"))
      (node (ref "IC26") (pin "3") (pinfunction "GND_3") (pintype "passive"))
      (node (ref "IC30") (pin "C5") (pinfunction "VSS_C5") (pintype "power_in"))
      (node (ref "IC30") (pin "F7") (pinfunction "VSS_F7") (pintype "power_in"))
      (node (ref "IC30") (pin "K3") (pinfunction "VSS_K3") (pintype "power_in"))
      (node (ref "IC30") (pin "K8") (pinfunction "VSS_K8") (pintype "power_in"))
      (node (ref "P10") (pin "4") (pinfunction "4_4") (pintype "passive"))
      (node (ref "P10") (pin "6") (pinfunction "6_6") (pintype "passive"))
      (node (ref "R1") (pin "1") (pinfunction "1_1") (pintype "passive"))
      (node (ref "R164") (pin "1") (pinfunction "1_1") (pintype "passive"))
      (node (ref "R170") (pin "2") (pinfunction "2_2") (pintype "passive"))
      (node (ref "R77") (pin "2") (pinfunction "2_2") (pintype "passive"))
    )
    (net (code "77") (name "Net-(IC6A-PC13{slash}NCS2)") (class "Default")
      (node (ref "IC6") (pin "D7") (pinfunction "PC13/NCS2_D7") (pintype "bidirectional"))
      (node (ref "R179") (pin "2") (pinfunction "2_2") (pintype "passive"))
    )
    (net (code "78") (name "Net-(IC6A-PC14{slash}NCS3{slash}NANDCS)") (class "Default")
      (node (ref "IC6") (pin "F8") (pinfunction "PC14/NCS3/NANDCS_F8") (pintype "bidirectional"))
      (node (ref "R177") (pin "2") (pinfunction "2_2") (pintype "passive"))
    )
    (net (code "79") (name "Net-(IC25-SO)") (class "Default")
      (node (ref "IC25") (pin "8") (pinfunction "SO_8") (pintype "output"))
      (node (ref "R250") (pin "1") (pinfunction "1_1") (pintype "passive"))
    )
    (net (code "80") (name "Net-(IC25-~{WP})") (class "Default")
      (node (ref "IC25") (pin "5") (pinfunction "~{WP}_5") (pintype "input"))
      (node (ref "R164") (pin "2") (pinfunction "2_2") (pintype "passive"))
      (node (ref "R165") (pin "1") (pinfunction "1_1") (pintype "passive"))
    )
    (net (code "81") (name "Net-(IC26A-Y)") (class "Default")
      (node (ref "IC26") (pin "4") (pinfunction "Y_4") (pintype "output"))
      (node (ref "IC30") (pin "C6") (pinfunction "~{CE}_C6") (pintype "input"))
    )
    (net (code "82") (name "Net-(IC30-~{WP})") (class "Default")
      (node (ref "IC30") (pin "C3") (pinfunction "~{WP}_C3") (pintype "input"))
      (node (ref "R167") (pin "1") (pinfunction "1_1") (pintype "passive"))
    )
    (net (code "83") (name "Net-(IC33E-IO_L12N_VRP_16)") (class "Default")
      (node (ref "IC33") (pin "F34") (pinfunction "IO_L12N_VRP_16_F34") (pintype "bidirectional"))
      (node (ref "R77") (pin "1") (pinfunction "1_1") (pintype "passive"))
    )
    (net (code "84") (name "Net-(IC33E-IO_L12P_VRN_16)") (class "Default")
      (node (ref "IC33") (pin "E34") (pinfunction "IO_L12P_VRN_16_E34") (pintype "bidirectional"))
      (node (ref "R75") (pin "1") (pinfunction "1_1") (pintype "passive"))
    )
    (net (code "85") (name "unconnected-(IC6A-BC1{slash}DQM3-PadE9)") (class "Default")
      (node (ref "IC6") (pin "E9") (pinfunction "BC1/DQM3_E9") (pintype "bidirectional"))
    )
    (net (code "86") (name "unconnected-(IC6A-PC0{slash}DQM2-PadA8)") (class "Default")
      (node (ref "IC6") (pin "A8") (pinfunction "PC0/DQM2_A8") (pintype "bidirectional"))
    )
    (net (code "87") (name "unconnected-(IC6A-PC6{slash}A23-PadD8)") (class "Default")
      (node (ref "IC6") (pin "D8") (pinfunction "PC6/A23_D8") (pintype "bidirectional"))
    )
    (net (code "88") (name "unconnected-(IC6A-PC9{slash}CFCE2{slash}RTS2-PadC7)") (class "Default")
      (node (ref "IC6") (pin "C7") (pinfunction "PC9/CFCE2/RTS2_C7") (pintype "bidirectional"))
    )
    (net (code "89") (name "unconnected-(IC6A-PC10{slash}NCS4{slash}CFCS0{slash}TCLK2-PadB6)") (class "Default")
      (node (ref "IC6") (pin "B6") (pinfunction "PC10/NCS4/CFCS0/TCLK2_B6") (pintype "bidirectional"))
    )
    (net (code "90") (name "unconnected-(IC6A-PC11{slash}NCS5{slash}CFCS1{slash}CTS2-PadB7)") (class "Default")
      (node (ref "IC6") (pin "B7") (pinfunction "PC11/NCS5/CFCS1/CTS2_B7") (pintype "bidirectional"))
    )
    (net (code "91") (name "unconnected-(IC6A-PC12{slash}A25{slash}CFRNW-PadA5)") (class "Default")
      (node (ref "IC6") (pin "A5") (pinfunction "PC12/A25/CFRNW_A5") (pintype "bidirectional"))
    )
    (net (code "92") (name "unconnected-(IC6G-EBI1_CAS-PadC11)") (class "Default")
      (node (ref "IC6") (pin "C11") (pinfunction "EBI1_CAS_C11") (pintype "output"))
    )
    (net (code "93") (name "unconnected-(IC6G-EBI1_DQM0-PadB11)") (class "Default")
      (node (ref "IC6") (pin "B11") (pinfunction "EBI1_DQM0_B11") (pintype "output"))
    )
    (net (code "94") (name "unconnected-(IC6G-EBI1_DQM1-PadD11)") (class "Default")
      (node (ref "IC6") (pin "D11") (pinfunction "EBI1_DQM1_D11") (pintype "output"))
    )
    (net (code "95") (name "unconnected-(IC6G-EBI1_DQS0-PadA11)") (class "Default")
      (node (ref "IC6") (pin "A11") (pinfunction "EBI1_DQS0_A11") (pintype "output"))
    )
    (net (code "96") (name "unconnected-(IC6G-EBI1_DQS1-PadE11)") (class "Default")
      (node (ref "IC6") (pin "E11") (pinfunction "EBI1_DQS1_E11") (pintype "output"))
    )
    (net (code "97") (name "unconnected-(IC6G-EBI1_NCS1{slash}SDCS-PadF10)") (class "Default")
      (node (ref "IC6") (pin "F10") (pinfunction "EBI1_NCS1/SDCS_F10") (pintype "output"))
    )
    (net (code "98") (name "unconnected-(IC6G-EBI1_NSDCK-PadA14)") (class "Default")
      (node (ref "IC6") (pin "A14") (pinfunction "EBI1_NSDCK_A14") (pintype "output"))
    )
    (net (code "99") (name "unconnected-(IC6G-EBI1_RAS-PadA12)") (class "Default")
      (node (ref "IC6") (pin "A12") (pinfunction "EBI1_RAS_A12") (pintype "output"))
    )
    (net (code "100") (name "unconnected-(IC6G-EBI1_SDA10-PadB9)") (class "Default")
      (node (ref "IC6") (pin "B9") (pinfunction "EBI1_SDA10_B9") (pintype "output"))
    )
    (net (code "101") (name "unconnected-(IC6G-EBI1_SDCK-PadA13)") (class "Default")
      (node (ref "IC6") (pin "A13") (pinfunction "EBI1_SDCK_A13") (pintype "output"))
    )
    (net (code "102") (name "unconnected-(IC6G-EBI1_SDCKE-PadB12)") (class "Default")
      (node (ref "IC6") (pin "B12") (pinfunction "EBI1_SDCKE_B12") (pintype "output"))
    )
    (net (code "103") (name "unconnected-(IC6G-EBI1_SDWE-PadF12)") (class "Default")
      (node (ref "IC6") (pin "F12") (pinfunction "EBI1_SDWE_F12") (pintype "output"))
    )
    (net (code "104") (name "unconnected-(IC30-~{LOCK}-PadG5)") (class "Default")
      (node (ref "IC30") (pin "G5") (pinfunction "~{LOCK}_G5") (pintype "input+no_connect"))
    )
    (net (code "105") (name "unconnected-(IC33D-IO_L3N_SM9N_15-PadM27)") (class "Default")
      (node (ref "IC33") (pin "M27") (pinfunction "IO_L3N_SM9N_15_M27") (pintype "bidirectional"))
    )
    (net (code "106") (name "unconnected-(IC33D-IO_L3P_SM9P_15-PadM26)") (class "Default")
      (node (ref "IC33") (pin "M26") (pinfunction "IO_L3P_SM9P_15_M26") (pintype "bidirectional"))
    )
    (net (code "107") (name "unconnected-(IC33D-IO_L4N_VREF_15-PadP30)") (class "Default")
      (node (ref "IC33") (pin "P30") (pinfunction "IO_L4N_VREF_15_P30") (pintype "bidirectional"))
    )
    (net (code "108") (name "unconnected-(IC33D-IO_L4P_15-PadP31)") (class "Default")
      (node (ref "IC33") (pin "P31") (pinfunction "IO_L4P_15_P31") (pintype "bidirectional"))
    )
    (net (code "109") (name "unconnected-(IC33D-IO_L5P_SM10P_15-PadN27)") (class "Default")
      (node (ref "IC33") (pin "N27") (pinfunction "IO_L5P_SM10P_15_N27") (pintype "bidirectional"))
    )
    (net (code "110") (name "unconnected-(IC33D-IO_L8N_SRCC_15-PadP32)") (class "Default")
      (node (ref "IC33") (pin "P32") (pinfunction "IO_L8N_SRCC_15_P32") (pintype "bidirectional"))
    )
    (net (code "111") (name "unconnected-(IC33D-IO_L8P_SRCC_15-PadN32)") (class "Default")
      (node (ref "IC33") (pin "N32") (pinfunction "IO_L8P_SRCC_15_N32") (pintype "bidirectional"))
    )
    (net (code "112") (name "unconnected-(IC33D-IO_L9N_MRCC_15-PadN29)") (class "Default")
      (node (ref "IC33") (pin "N29") (pinfunction "IO_L9N_MRCC_15_N29") (pintype "bidirectional"))
    )
    (net (code "113") (name "unconnected-(IC33D-IO_L9P_MRCC_15-PadN28)") (class "Default")
      (node (ref "IC33") (pin "N28") (pinfunction "IO_L9P_MRCC_15_N28") (pintype "bidirectional"))
    )
    (net (code "114") (name "unconnected-(IC33D-IO_L10N_MRCC_15-PadM33)") (class "Default")
      (node (ref "IC33") (pin "M33") (pinfunction "IO_L10N_MRCC_15_M33") (pintype "bidirectional"))
    )
    (net (code "115") (name "unconnected-(IC33D-IO_L11N_SRCC_15-PadL30)") (class "Default")
      (node (ref "IC33") (pin "L30") (pinfunction "IO_L11N_SRCC_15_L30") (pintype "bidirectional"))
    )
    (net (code "116") (name "unconnected-(IC33D-IO_L11P_SRCC_15-PadL29)") (class "Default")
      (node (ref "IC33") (pin "L29") (pinfunction "IO_L11P_SRCC_15_L29") (pintype "bidirectional"))
    )
    (net (code "117") (name "unconnected-(IC33E-IO_L9N_MRCC_16-PadK27)") (class "Default")
      (node (ref "IC33") (pin "K27") (pinfunction "IO_L9N_MRCC_16_K27") (pintype "bidirectional"))
    )
    (net (code "118") (name "unconnected-(IC33E-IO_L9P_MRCC_16-PadK26)") (class "Default")
      (node (ref "IC33") (pin "K26") (pinfunction "IO_L9P_MRCC_16_K26") (pintype "bidirectional"))
    )
    (net (code "119") (name "unconnected-(IC33E-IO_L10N_MRCC_16-PadG33)") (class "Default")
      (node (ref "IC33") (pin "G33") (pinfunction "IO_L10N_MRCC_16_G33") (pintype "bidirectional"))
    )
    (net (code "120") (name "unconnected-(IC33E-IO_L10P_MRCC_16-PadF33)") (class "Default")
      (node (ref "IC33") (pin "F33") (pinfunction "IO_L10P_MRCC_16_F33") (pintype "bidirectional"))
    )
    (net (code "121") (name "unconnected-(IC33E-IO_L11N_SRCC_16-PadE31)") (class "Default")
      (node (ref "IC33") (pin "E31") (pinfunction "IO_L11N_SRCC_16_E31") (pintype "bidirectional"))
    )
    (net (code "122") (name "unconnected-(IC33E-IO_L11P_SRCC_16-PadF31)") (class "Default")
      (node (ref "IC33") (pin "F31") (pinfunction "IO_L11P_SRCC_16_F31") (pintype "bidirectional"))
    )
  )
)
